# V_5.net
KiCad netlist of a schematic drawn in Altium Designer
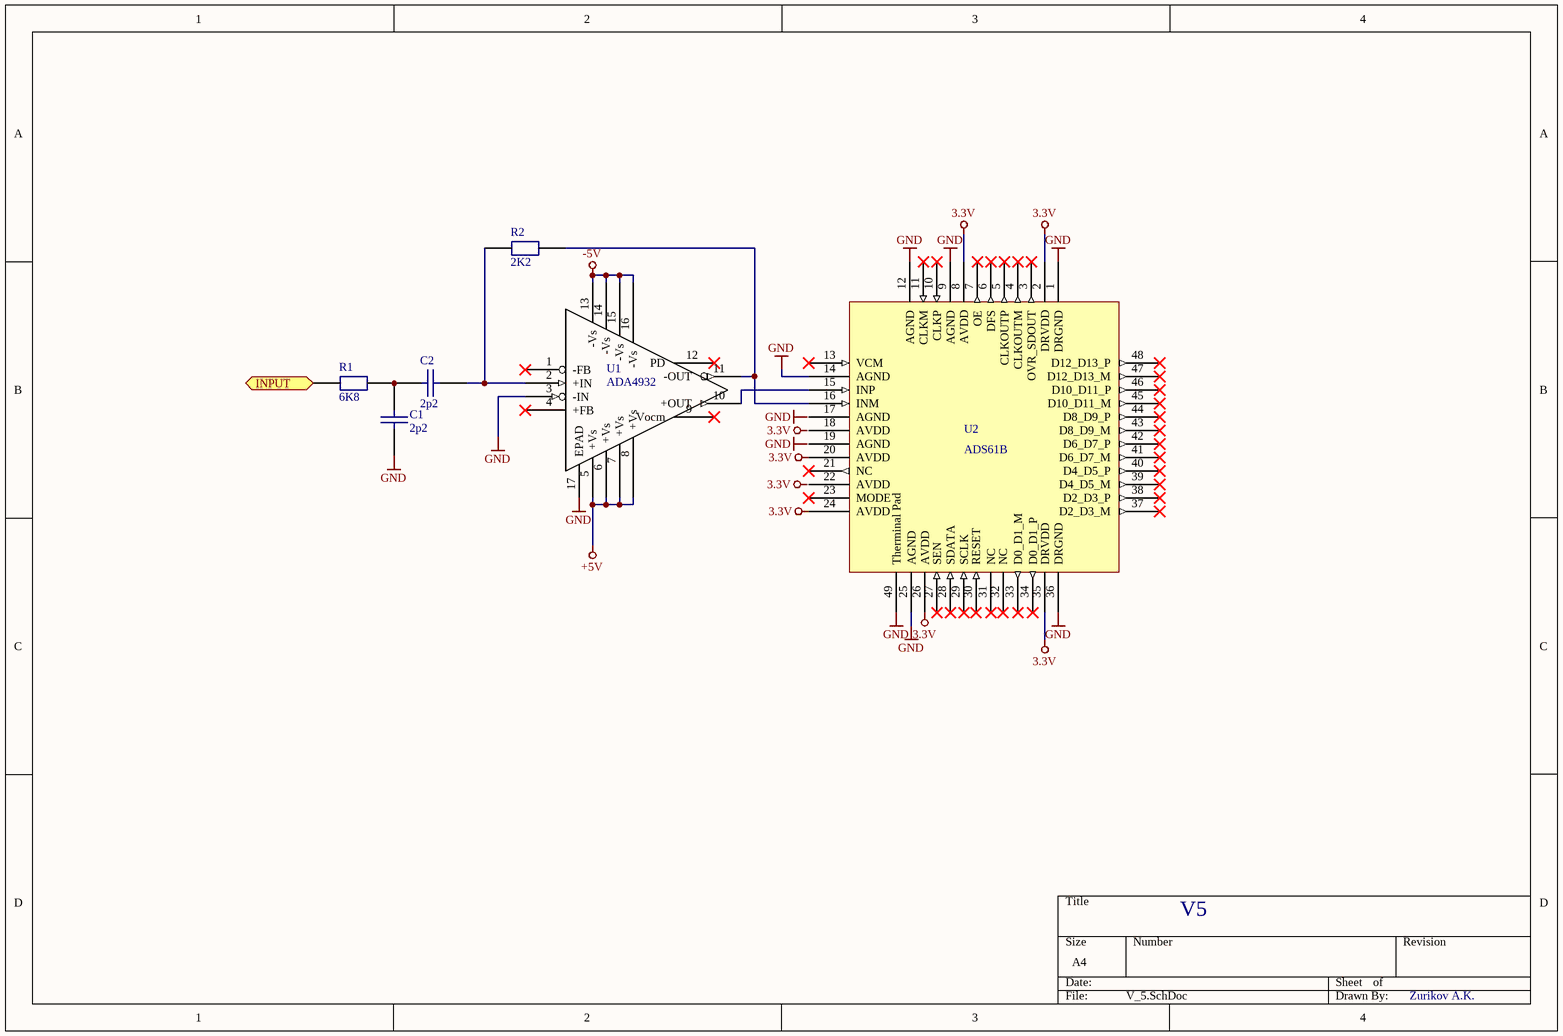
[diagram p0: V_5.SchDoc]

(export (version "E")
  (design (tool "Eeschema 10.0.6"))
  (components
    (comp (ref "C1") (value "2p2") (footprint "Capacitor") (libsource (lib "V_1") (part "Cap")))
    (comp (ref "C2") (value "2p2") (footprint "Capacitor") (libsource (lib "V_1") (part "Cap")))
    (comp (ref "R1") (value "6K8") (footprint "Resistor") (libsource (lib "V_1") (part "Res")))
    (comp (ref "R2") (value "2K2") (footprint "Resistor") (libsource (lib "V_1") (part "Res")))
    (comp (ref "U1") (value "ADA4932") (footprint "ADA4932") (libsource (lib "V_1") (part "ADA4932")))
    (comp (ref "U2") (value "ADS61B") (footprint "ADS61B49") (libsource (lib "V_1") (part "ADS61B49")))
  )
  (nets
    (net (code "1") (name "+5V") (class "Default")
      (node (ref "U1") (pin "5") (pinfunction "+Vs_5") (pintype "power_in"))
      (node (ref "U1") (pin "6") (pinfunction "+Vs_6") (pintype "power_in"))
      (node (ref "U1") (pin "7") (pinfunction "+Vs_7") (pintype "power_in"))
      (node (ref "U1") (pin "8") (pinfunction "+Vs_8") (pintype "power_in"))
    )
    (net (code "2") (name "-5V") (class "Default")
      (node (ref "U1") (pin "13") (pinfunction "-Vs_13") (pintype "power_in"))
      (node (ref "U1") (pin "14") (pinfunction "-Vs_14") (pintype "power_in"))
      (node (ref "U1") (pin "15") (pinfunction "-Vs_15") (pintype "power_in"))
      (node (ref "U1") (pin "16") (pinfunction "-Vs_16") (pintype "power_in"))
    )
    (net (code "3") (name "/INPUT") (class "Default")
      (node (ref "R1") (pin "1") (pinfunction "1_1") (pintype "passive"))
    )
    (net (code "4") (name "3.3V") (class "Default")
      (node (ref "U2") (pin "2") (pinfunction "DRVDD_2") (pintype "power_in"))
      (node (ref "U2") (pin "20") (pinfunction "AVDD_20") (pintype "power_in"))
      (node (ref "U2") (pin "24") (pinfunction "AVDD_24") (pintype "power_in"))
      (node (ref "U2") (pin "26") (pinfunction "AVDD_26") (pintype "power_in"))
      (node (ref "U2") (pin "35") (pinfunction "DRVDD_35") (pintype "power_in"))
      (node (ref "U2") (pin "8") (pinfunction "AVDD_8") (pintype "power_in"))
    )
    (net (code "5") (name "GND") (class "Default")
      (node (ref "C1") (pin "1") (pinfunction "1_1") (pintype "passive"))
      (node (ref "U1") (pin "17") (pinfunction "EPAD_17") (pintype "power_in"))
      (node (ref "U1") (pin "3") (pinfunction "-IN_3") (pintype "input"))
      (node (ref "U2") (pin "1") (pinfunction "DRGND_1") (pintype "power_in"))
      (node (ref "U2") (pin "12") (pinfunction "AGND_12") (pintype "power_in"))
      (node (ref "U2") (pin "14") (pinfunction "AGND_14") (pintype "power_in"))
      (node (ref "U2") (pin "25") (pinfunction "AGND_25") (pintype "power_in"))
      (node (ref "U2") (pin "36") (pinfunction "DRGND_36") (pintype "power_in"))
      (node (ref "U2") (pin "49") (pinfunction "Therminal_Pad_49") (pintype "power_in"))
      (node (ref "U2") (pin "9") (pinfunction "AGND_9") (pintype "power_in"))
    )
    (net (code "6") (name "Net-(C1-Pad2)") (class "Default")
      (node (ref "C1") (pin "2") (pinfunction "2_2") (pintype "passive"))
      (node (ref "C2") (pin "2") (pinfunction "2_2") (pintype "passive"))
      (node (ref "R1") (pin "2") (pinfunction "2_2") (pintype "passive"))
    )
    (net (code "7") (name "Net-(U1-+IN)") (class "Default")
      (node (ref "C2") (pin "1") (pinfunction "1_1") (pintype "passive"))
      (node (ref "R2") (pin "1") (pinfunction "1_1") (pintype "passive"))
      (node (ref "U1") (pin "2") (pinfunction "+IN_2") (pintype "input"))
    )
    (net (code "8") (name "Net-(U1-+OUT)") (class "Default")
      (node (ref "U1") (pin "10") (pinfunction "+OUT_10") (pintype "output"))
      (node (ref "U2") (pin "15") (pinfunction "INP_15") (pintype "input"))
    )
    (net (code "9") (name "Net-(U1--OUT)") (class "Default")
      (node (ref "R2") (pin "2") (pinfunction "2_2") (pintype "passive"))
      (node (ref "U1") (pin "11") (pinfunction "-OUT_11") (pintype "output"))
      (node (ref "U2") (pin "16") (pinfunction "INM_16") (pintype "input"))
    )
    (net (code "10") (name "unconnected-(U1-+FB-Pad4)") (class "Default")
      (node (ref "U1") (pin "4") (pinfunction "+FB_4") (pintype "passive+no_connect"))
    )
    (net (code "11") (name "unconnected-(U1--FB-Pad1)") (class "Default")
      (node (ref "U1") (pin "1") (pinfunction "-FB_1") (pintype "passive+no_connect"))
    )
    (net (code "12") (name "unconnected-(U1-PD-Pad12)") (class "Default")
      (node (ref "U1") (pin "12") (pinfunction "PD_12") (pintype "passive+no_connect"))
    )
    (net (code "13") (name "unconnected-(U1-Vocm-Pad9)") (class "Default")
      (node (ref "U1") (pin "9") (pinfunction "Vocm_9") (pintype "power_in+no_connect"))
    )
    (net (code "14") (name "unconnected-(U2-AGND-Pad17)") (class "Default")
      (node (ref "U2") (pin "17") (pinfunction "AGND_17") (pintype "power_in"))
    )
    (net (code "15") (name "unconnected-(U2-AGND-Pad19)") (class "Default")
      (node (ref "U2") (pin "19") (pinfunction "AGND_19") (pintype "power_in"))
    )
    (net (code "16") (name "unconnected-(U2-AVDD-Pad18)") (class "Default")
      (node (ref "U2") (pin "18") (pinfunction "AVDD_18") (pintype "power_in"))
    )
    (net (code "17") (name "unconnected-(U2-AVDD-Pad22)") (class "Default")
      (node (ref "U2") (pin "22") (pinfunction "AVDD_22") (pintype "power_in"))
    )
    (net (code "18") (name "unconnected-(U2-CLKM-Pad11)") (class "Default")
      (node (ref "U2") (pin "11") (pinfunction "CLKM_11") (pintype "input+no_connect"))
    )
    (net (code "19") (name "unconnected-(U2-CLKOUTM-Pad4)") (class "Default")
      (node (ref "U2") (pin "4") (pinfunction "CLKOUTM_4") (pintype "output+no_connect"))
    )
    (net (code "20") (name "unconnected-(U2-CLKOUTP-Pad5)") (class "Default")
      (node (ref "U2") (pin "5") (pinfunction "CLKOUTP_5") (pintype "output+no_connect"))
    )
    (net (code "21") (name "unconnected-(U2-CLKP-Pad10)") (class "Default")
      (node (ref "U2") (pin "10") (pinfunction "CLKP_10") (pintype "input+no_connect"))
    )
    (net (code "22") (name "unconnected-(U2-D0_D1_M-Pad33)") (class "Default")
      (node (ref "U2") (pin "33") (pinfunction "D0_D1_M_33") (pintype "output+no_connect"))
    )
    (net (code "23") (name "unconnected-(U2-D0_D1_P-Pad34)") (class "Default")
      (node (ref "U2") (pin "34") (pinfunction "D0_D1_P_34") (pintype "output+no_connect"))
    )
    (net (code "24") (name "unconnected-(U2-D2_D3_M-Pad37)") (class "Default")
      (node (ref "U2") (pin "37") (pinfunction "D2_D3_M_37") (pintype "output+no_connect"))
    )
    (net (code "25") (name "unconnected-(U2-D2_D3_P-Pad38)") (class "Default")
      (node (ref "U2") (pin "38") (pinfunction "D2_D3_P_38") (pintype "output+no_connect"))
    )
    (net (code "26") (name "unconnected-(U2-D4_D5_M-Pad39)") (class "Default")
      (node (ref "U2") (pin "39") (pinfunction "D4_D5_M_39") (pintype "output+no_connect"))
    )
    (net (code "27") (name "unconnected-(U2-D4_D5_P-Pad40)") (class "Default")
      (node (ref "U2") (pin "40") (pinfunction "D4_D5_P_40") (pintype "output+no_connect"))
    )
    (net (code "28") (name "unconnected-(U2-D6_D7_M-Pad41)") (class "Default")
      (node (ref "U2") (pin "41") (pinfunction "D6_D7_M_41") (pintype "output+no_connect"))
    )
    (net (code "29") (name "unconnected-(U2-D6_D7_P-Pad42)") (class "Default")
      (node (ref "U2") (pin "42") (pinfunction "D6_D7_P_42") (pintype "output+no_connect"))
    )
    (net (code "30") (name "unconnected-(U2-D8_D9_M-Pad43)") (class "Default")
      (node (ref "U2") (pin "43") (pinfunction "D8_D9_M_43") (pintype "output+no_connect"))
    )
    (net (code "31") (name "unconnected-(U2-D8_D9_P-Pad44)") (class "Default")
      (node (ref "U2") (pin "44") (pinfunction "D8_D9_P_44") (pintype "output+no_connect"))
    )
    (net (code "32") (name "unconnected-(U2-D10_D11_M-Pad45)") (class "Default")
      (node (ref "U2") (pin "45") (pinfunction "D10_D11_M_45") (pintype "output+no_connect"))
    )
    (net (code "33") (name "unconnected-(U2-D10_D11_P-Pad46)") (class "Default")
      (node (ref "U2") (pin "46") (pinfunction "D10_D11_P_46") (pintype "output+no_connect"))
    )
    (net (code "34") (name "unconnected-(U2-D12_D13_M-Pad47)") (class "Default")
      (node (ref "U2") (pin "47") (pinfunction "D12_D13_M_47") (pintype "output+no_connect"))
    )
    (net (code "35") (name "unconnected-(U2-D12_D13_P-Pad48)") (class "Default")
      (node (ref "U2") (pin "48") (pinfunction "D12_D13_P_48") (pintype "output+no_connect"))
    )
    (net (code "36") (name "unconnected-(U2-DFS-Pad6)") (class "Default")
      (node (ref "U2") (pin "6") (pinfunction "DFS_6") (pintype "output+no_connect"))
    )
    (net (code "37") (name "unconnected-(U2-MODE-Pad23)") (class "Default")
      (node (ref "U2") (pin "23") (pinfunction "MODE_23") (pintype "passive+no_connect"))
    )
    (net (code "38") (name "unconnected-(U2-NC-Pad21)") (class "Default")
      (node (ref "U2") (pin "21") (pinfunction "NC_21") (pintype "output+no_connect"))
    )
    (net (code "39") (name "unconnected-(U2-NC-Pad31)") (class "Default")
      (node (ref "U2") (pin "31") (pinfunction "NC_31") (pintype "passive+no_connect"))
    )
    (net (code "40") (name "unconnected-(U2-NC-Pad32)") (class "Default")
      (node (ref "U2") (pin "32") (pinfunction "NC_32") (pintype "passive+no_connect"))
    )
    (net (code "41") (name "unconnected-(U2-OE-Pad7)") (class "Default")
      (node (ref "U2") (pin "7") (pinfunction "OE_7") (pintype "output+no_connect"))
    )
    (net (code "42") (name "unconnected-(U2-OVR_SDOUT-Pad3)") (class "Default")
      (node (ref "U2") (pin "3") (pinfunction "OVR_SDOUT_3") (pintype "output+no_connect"))
    )
    (net (code "43") (name "unconnected-(U2-RESET-Pad30)") (class "Default")
      (node (ref "U2") (pin "30") (pinfunction "RESET_30") (pintype "input+no_connect"))
    )
    (net (code "44") (name "unconnected-(U2-SCLK-Pad29)") (class "Default")
      (node (ref "U2") (pin "29") (pinfunction "SCLK_29") (pintype "input+no_connect"))
    )
    (net (code "45") (name "unconnected-(U2-SDATA-Pad28)") (class "Default")
      (node (ref "U2") (pin "28") (pinfunction "SDATA_28") (pintype "input+no_connect"))
    )
    (net (code "46") (name "unconnected-(U2-SEN-Pad27)") (class "Default")
      (node (ref "U2") (pin "27") (pinfunction "SEN_27") (pintype "input+no_connect"))
    )
    (net (code "47") (name "unconnected-(U2-VCM-Pad13)") (class "Default")
      (node (ref "U2") (pin "13") (pinfunction "VCM_13") (pintype "input+no_connect"))
    )
  )
)
